# sold.net
KiCad netlist of a schematic drawn in EAGLE
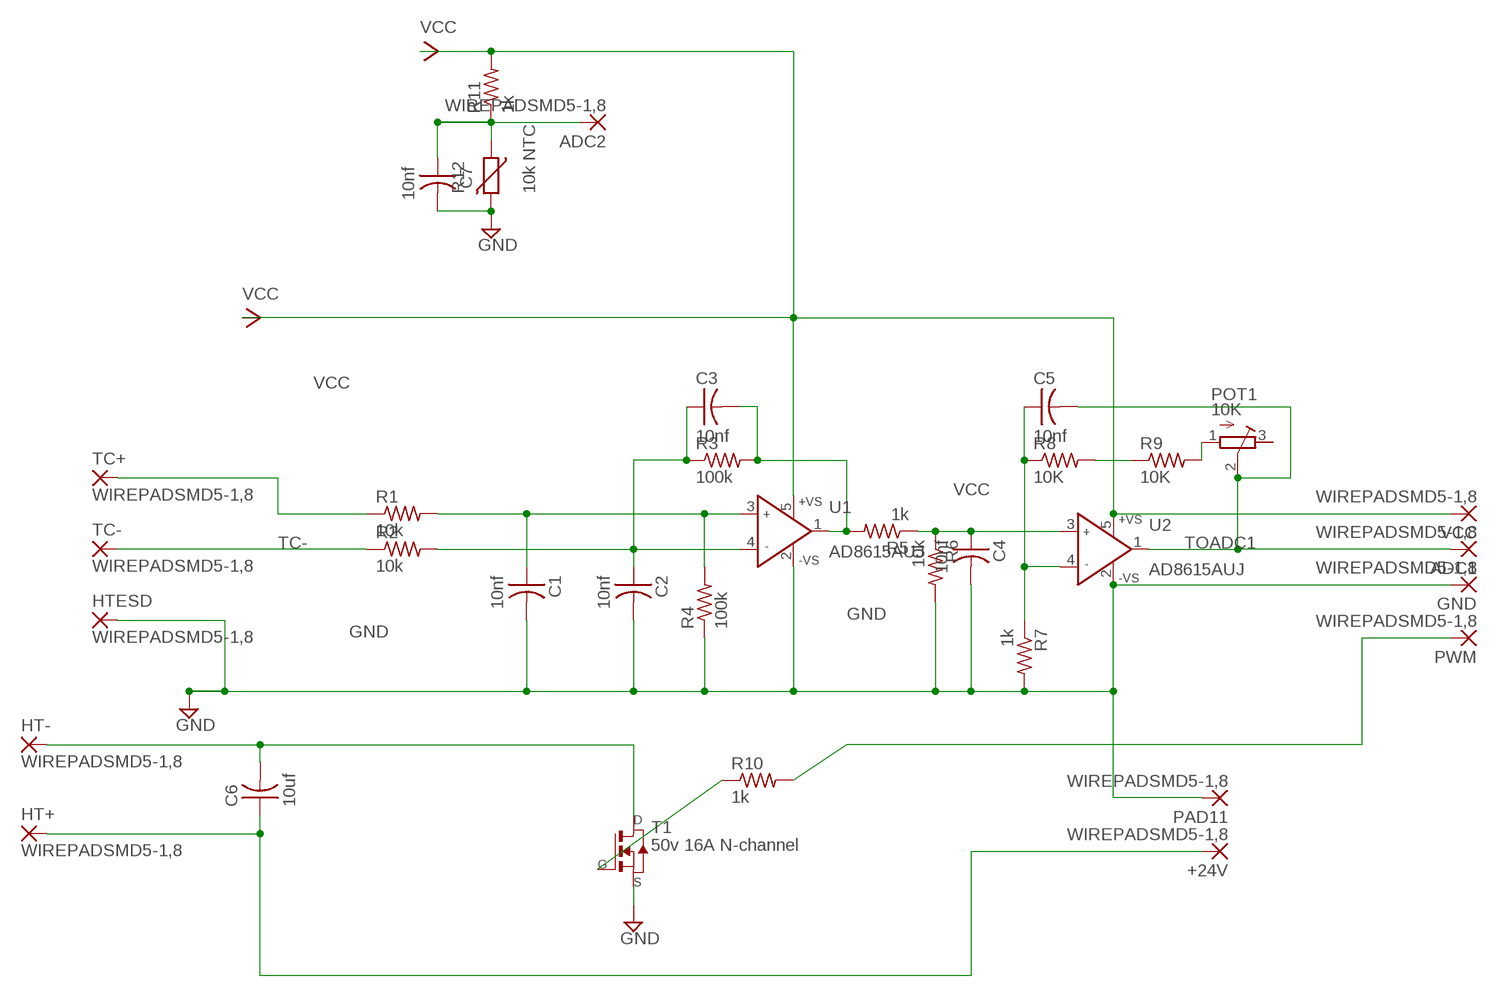
[diagram p0: schematic, sheet 1]

(export (version "E")
  (design (tool "Eeschema 10.0.6"))
  (components
    (comp (ref "+24V")
      (value "WIREPADSMD5-1,8")
      (footprint "eagle-import:5-1,8")
      (libsource (lib "eagle-import") (part "WIREPADSMD5-1,8"))
    )
    (comp (ref "ADC1")
      (value "WIREPADSMD5-1,8")
      (footprint "eagle-import:5-1,8")
      (libsource (lib "eagle-import") (part "WIREPADSMD5-1,8"))
    )
    (comp (ref "ADC2")
      (value "WIREPADSMD5-1,8")
      (footprint "eagle-import:5-1,8")
      (libsource (lib "eagle-import") (part "WIREPADSMD5-1,8"))
    )
    (comp (ref "C1")
      (value "10nf")
      (footprint "eagle-import:C1206FAB")
      (libsource (lib "eagle-import") (part "CAP-US1206FAB"))
    )
    (comp (ref "C2")
      (value "10nf")
      (footprint "eagle-import:C1206FAB")
      (libsource (lib "eagle-import") (part "CAP-US1206FAB"))
    )
    (comp (ref "C3")
      (value "10nf")
      (footprint "eagle-import:C1206FAB")
      (libsource (lib "eagle-import") (part "CAP-US1206FAB"))
    )
    (comp (ref "C4")
      (value "10nf")
      (footprint "eagle-import:C1206FAB")
      (libsource (lib "eagle-import") (part "CAP-US1206FAB"))
    )
    (comp (ref "C5")
      (value "10nf")
      (footprint "eagle-import:C1206FAB")
      (libsource (lib "eagle-import") (part "CAP-US1206FAB"))
    )
    (comp (ref "C6")
      (value "10uf")
      (footprint "eagle-import:C1206FAB")
      (libsource (lib "eagle-import") (part "CAP-US1206FAB"))
    )
    (comp (ref "C7")
      (value "10nf")
      (footprint "eagle-import:C1206FAB")
      (libsource (lib "eagle-import") (part "CAP-US1206FAB"))
    )
    (comp (ref "GND")
      (value "WIREPADSMD5-1,8")
      (footprint "eagle-import:5-1,8")
      (libsource (lib "eagle-import") (part "WIREPADSMD5-1,8"))
    )
    (comp (ref "HT+")
      (value "WIREPADSMD5-1,8")
      (footprint "eagle-import:5-1,8")
      (libsource (lib "eagle-import") (part "WIREPADSMD5-1,8"))
    )
    (comp (ref "HT-")
      (value "WIREPADSMD5-1,8")
      (footprint "eagle-import:5-1,8")
      (libsource (lib "eagle-import") (part "WIREPADSMD5-1,8"))
    )
    (comp (ref "HTESD")
      (value "WIREPADSMD5-1,8")
      (footprint "eagle-import:5-1,8")
      (libsource (lib "eagle-import") (part "WIREPADSMD5-1,8"))
    )
    (comp (ref "PAD11")
      (value "WIREPADSMD5-1,8")
      (footprint "eagle-import:5-1,8")
      (libsource (lib "eagle-import") (part "WIREPADSMD5-1,8"))
    )
    (comp (ref "POT1")
      (value "10K")
      (footprint "eagle-import:RTRIM3103")
      (libsource (lib "eagle-import") (part "R-TRIMM3103"))
    )
    (comp (ref "PWM")
      (value "WIREPADSMD5-1,8")
      (footprint "eagle-import:5-1,8")
      (libsource (lib "eagle-import") (part "WIREPADSMD5-1,8"))
    )
    (comp (ref "R1")
      (value "10k")
      (footprint "eagle-import:R1206FAB")
      (libsource (lib "eagle-import") (part "RES-US1206FAB"))
    )
    (comp (ref "R2")
      (value "10k")
      (footprint "eagle-import:R1206FAB")
      (libsource (lib "eagle-import") (part "RES-US1206FAB"))
    )
    (comp (ref "R3")
      (value "100k")
      (footprint "eagle-import:R1206FAB")
      (libsource (lib "eagle-import") (part "RES-US1206FAB"))
    )
    (comp (ref "R4")
      (value "100k")
      (footprint "eagle-import:R1206FAB")
      (libsource (lib "eagle-import") (part "RES-US1206FAB"))
    )
    (comp (ref "R5")
      (value "1k")
      (footprint "eagle-import:R1206FAB")
      (libsource (lib "eagle-import") (part "RES-US1206FAB"))
    )
    (comp (ref "R6")
      (value "10k")
      (footprint "eagle-import:R1206FAB")
      (libsource (lib "eagle-import") (part "RES-US1206FAB"))
    )
    (comp (ref "R7")
      (value "1k")
      (footprint "eagle-import:R1206FAB")
      (libsource (lib "eagle-import") (part "RES-US1206FAB"))
    )
    (comp (ref "R8")
      (value "10K")
      (footprint "eagle-import:R1206FAB")
      (libsource (lib "eagle-import") (part "RES-US1206FAB"))
    )
    (comp (ref "R9")
      (value "10K")
      (footprint "eagle-import:R1206FAB")
      (libsource (lib "eagle-import") (part "RES-US1206FAB"))
    )
    (comp (ref "R10")
      (value "1k")
      (footprint "eagle-import:R1206FAB")
      (libsource (lib "eagle-import") (part "RES-US1206FAB"))
    )
    (comp (ref "R11")
      (value "1k")
      (footprint "eagle-import:R1206FAB")
      (libsource (lib "eagle-import") (part "RES-US1206FAB"))
    )
    (comp (ref "R12")
      (value "10k NTC")
      (footprint "eagle-import:CT_CN1206")
      (libsource (lib "eagle-import") (part "VARISTORCN1206"))
    )
    (comp (ref "T1")
      (value "50v 16A N-channel")
      (footprint "eagle-import:TO252")
      (libsource (lib "eagle-import") (part "NMOSFETTO252"))
    )
    (comp (ref "TC+")
      (value "WIREPADSMD5-1,8")
      (footprint "eagle-import:5-1,8")
      (libsource (lib "eagle-import") (part "WIREPADSMD5-1,8"))
    )
    (comp (ref "TC-")
      (value "WIREPADSMD5-1,8")
      (footprint "eagle-import:5-1,8")
      (libsource (lib "eagle-import") (part "WIREPADSMD5-1,8"))
    )
    (comp (ref "U1")
      (value "AD8615AUJ")
      (footprint "eagle-import:TSOT23-5")
      (libsource (lib "eagle-import") (part "AD8615UJA"))
    )
    (comp (ref "U2")
      (value "AD8615AUJ")
      (footprint "eagle-import:TSOT23-5")
      (libsource (lib "eagle-import") (part "AD8615UJA"))
    )
    (comp (ref "VCC")
      (value "WIREPADSMD5-1,8")
      (footprint "eagle-import:5-1,8")
      (libsource (lib "eagle-import") (part "WIREPADSMD5-1,8"))
    )
  )
  (nets
    (net (code "1") (name "/TC-") (class "Default")
      (node (ref "R2") (pin "1") (pinfunction "1_1") (pintype "passive"))
      (node (ref "TC-") (pin "1") (pinfunction "P_1") (pintype "passive"))
    )
    (net (code "2") (name "/TOADC1") (class "Default")
      (node (ref "ADC1") (pin "1") (pinfunction "P_1") (pintype "passive"))
      (node (ref "C5") (pin "2") (pinfunction "2_2") (pintype "passive"))
      (node (ref "POT1") (pin "2") (pinfunction "S_2") (pintype "passive"))
      (node (ref "U2") (pin "1") (pinfunction "OUT_1") (pintype "output"))
    )
    (net (code "3") (name "GND") (class "Default")
      (node (ref "C1") (pin "2") (pinfunction "2_2") (pintype "passive"))
      (node (ref "C2") (pin "2") (pinfunction "2_2") (pintype "passive"))
      (node (ref "C4") (pin "2") (pinfunction "2_2") (pintype "passive"))
      (node (ref "C7") (pin "2") (pinfunction "2_2") (pintype "passive"))
      (node (ref "GND") (pin "1") (pinfunction "P_1") (pintype "passive"))
      (node (ref "HTESD") (pin "1") (pinfunction "P_1") (pintype "passive"))
      (node (ref "PAD11") (pin "1") (pinfunction "P_1") (pintype "passive"))
      (node (ref "R12") (pin "2") (pinfunction "2_2") (pintype "passive"))
      (node (ref "R4") (pin "1") (pinfunction "1_1") (pintype "passive"))
      (node (ref "R6") (pin "2") (pinfunction "2_2") (pintype "passive"))
      (node (ref "R7") (pin "2") (pinfunction "2_2") (pintype "passive"))
      (node (ref "T1") (pin "2") (pinfunction "S_2") (pintype "passive"))
      (node (ref "U1") (pin "2") (pinfunction "-VS_2") (pintype "input"))
      (node (ref "U2") (pin "2") (pinfunction "-VS_2") (pintype "input"))
    )
    (net (code "4") (name "Net-(+24V-P)") (class "Default")
      (node (ref "+24V") (pin "1") (pinfunction "P_1") (pintype "passive"))
      (node (ref "C6") (pin "1") (pinfunction "1_1") (pintype "passive"))
      (node (ref "HT+") (pin "1") (pinfunction "P_1") (pintype "passive"))
    )
    (net (code "5") (name "Net-(ADC2-P)") (class "Default")
      (node (ref "ADC2") (pin "1") (pinfunction "P_1") (pintype "passive"))
      (node (ref "C7") (pin "1") (pinfunction "1_1") (pintype "passive"))
      (node (ref "R11") (pin "1") (pinfunction "1_1") (pintype "passive"))
      (node (ref "R12") (pin "1") (pinfunction "1_1") (pintype "passive"))
    )
    (net (code "6") (name "Net-(HT--P)") (class "Default")
      (node (ref "C6") (pin "2") (pinfunction "2_2") (pintype "passive"))
      (node (ref "HT-") (pin "1") (pinfunction "P_1") (pintype "passive"))
      (node (ref "T1") (pin "3") (pinfunction "D_3") (pintype "passive"))
    )
    (net (code "7") (name "Net-(POT1-A)") (class "Default")
      (node (ref "POT1") (pin "1") (pinfunction "A_1") (pintype "passive"))
      (node (ref "R9") (pin "2") (pinfunction "2_2") (pintype "passive"))
    )
    (net (code "8") (name "Net-(PWM-P)") (class "Default")
      (node (ref "PWM") (pin "1") (pinfunction "P_1") (pintype "passive"))
      (node (ref "R10") (pin "2") (pinfunction "2_2") (pintype "passive"))
    )
    (net (code "9") (name "Net-(R8-Pad2)") (class "Default")
      (node (ref "R8") (pin "2") (pinfunction "2_2") (pintype "passive"))
      (node (ref "R9") (pin "1") (pinfunction "1_1") (pintype "passive"))
    )
    (net (code "10") (name "Net-(T1-G)") (class "Default")
      (node (ref "R10") (pin "1") (pinfunction "1_1") (pintype "passive"))
      (node (ref "T1") (pin "1") (pinfunction "G_1") (pintype "passive"))
    )
    (net (code "11") (name "Net-(TC+-P)") (class "Default")
      (node (ref "R1") (pin "1") (pinfunction "1_1") (pintype "passive"))
      (node (ref "TC+") (pin "1") (pinfunction "P_1") (pintype "passive"))
    )
    (net (code "12") (name "Net-(U1-IN+)") (class "Default")
      (node (ref "C1") (pin "1") (pinfunction "1_1") (pintype "passive"))
      (node (ref "R1") (pin "2") (pinfunction "2_2") (pintype "passive"))
      (node (ref "R4") (pin "2") (pinfunction "2_2") (pintype "passive"))
      (node (ref "U1") (pin "3") (pinfunction "IN+_3") (pintype "input"))
    )
    (net (code "13") (name "Net-(U1-IN-)") (class "Default")
      (node (ref "C2") (pin "1") (pinfunction "1_1") (pintype "passive"))
      (node (ref "C3") (pin "1") (pinfunction "1_1") (pintype "passive"))
      (node (ref "R2") (pin "2") (pinfunction "2_2") (pintype "passive"))
      (node (ref "R3") (pin "1") (pinfunction "1_1") (pintype "passive"))
      (node (ref "U1") (pin "4") (pinfunction "IN-_4") (pintype "input"))
    )
    (net (code "14") (name "Net-(U1-OUT)") (class "Default")
      (node (ref "C3") (pin "2") (pinfunction "2_2") (pintype "passive"))
      (node (ref "R3") (pin "2") (pinfunction "2_2") (pintype "passive"))
      (node (ref "R5") (pin "2") (pinfunction "2_2") (pintype "passive"))
      (node (ref "U1") (pin "1") (pinfunction "OUT_1") (pintype "output"))
    )
    (net (code "15") (name "Net-(U2-IN+)") (class "Default")
      (node (ref "C4") (pin "1") (pinfunction "1_1") (pintype "passive"))
      (node (ref "R5") (pin "1") (pinfunction "1_1") (pintype "passive"))
      (node (ref "R6") (pin "1") (pinfunction "1_1") (pintype "passive"))
      (node (ref "U2") (pin "3") (pinfunction "IN+_3") (pintype "input"))
    )
    (net (code "16") (name "Net-(U2-IN-)") (class "Default")
      (node (ref "C5") (pin "1") (pinfunction "1_1") (pintype "passive"))
      (node (ref "R7") (pin "1") (pinfunction "1_1") (pintype "passive"))
      (node (ref "R8") (pin "1") (pinfunction "1_1") (pintype "passive"))
      (node (ref "U2") (pin "4") (pinfunction "IN-_4") (pintype "input"))
    )
    (net (code "17") (name "VCC") (class "Default")
      (node (ref "R11") (pin "2") (pinfunction "2_2") (pintype "passive"))
      (node (ref "U1") (pin "5") (pinfunction "+VS_5") (pintype "input"))
      (node (ref "U2") (pin "5") (pinfunction "+VS_5") (pintype "input"))
      (node (ref "VCC") (pin "1") (pinfunction "P_1") (pintype "passive"))
    )
    (net (code "18") (name "unconnected-(POT1-E-Pad3)") (class "Default")
      (node (ref "POT1") (pin "3") (pinfunction "E_3") (pintype "passive"))
    )
  )
)
